# vl822.net
KiCad netlist of a schematic drawn in Altium Designer
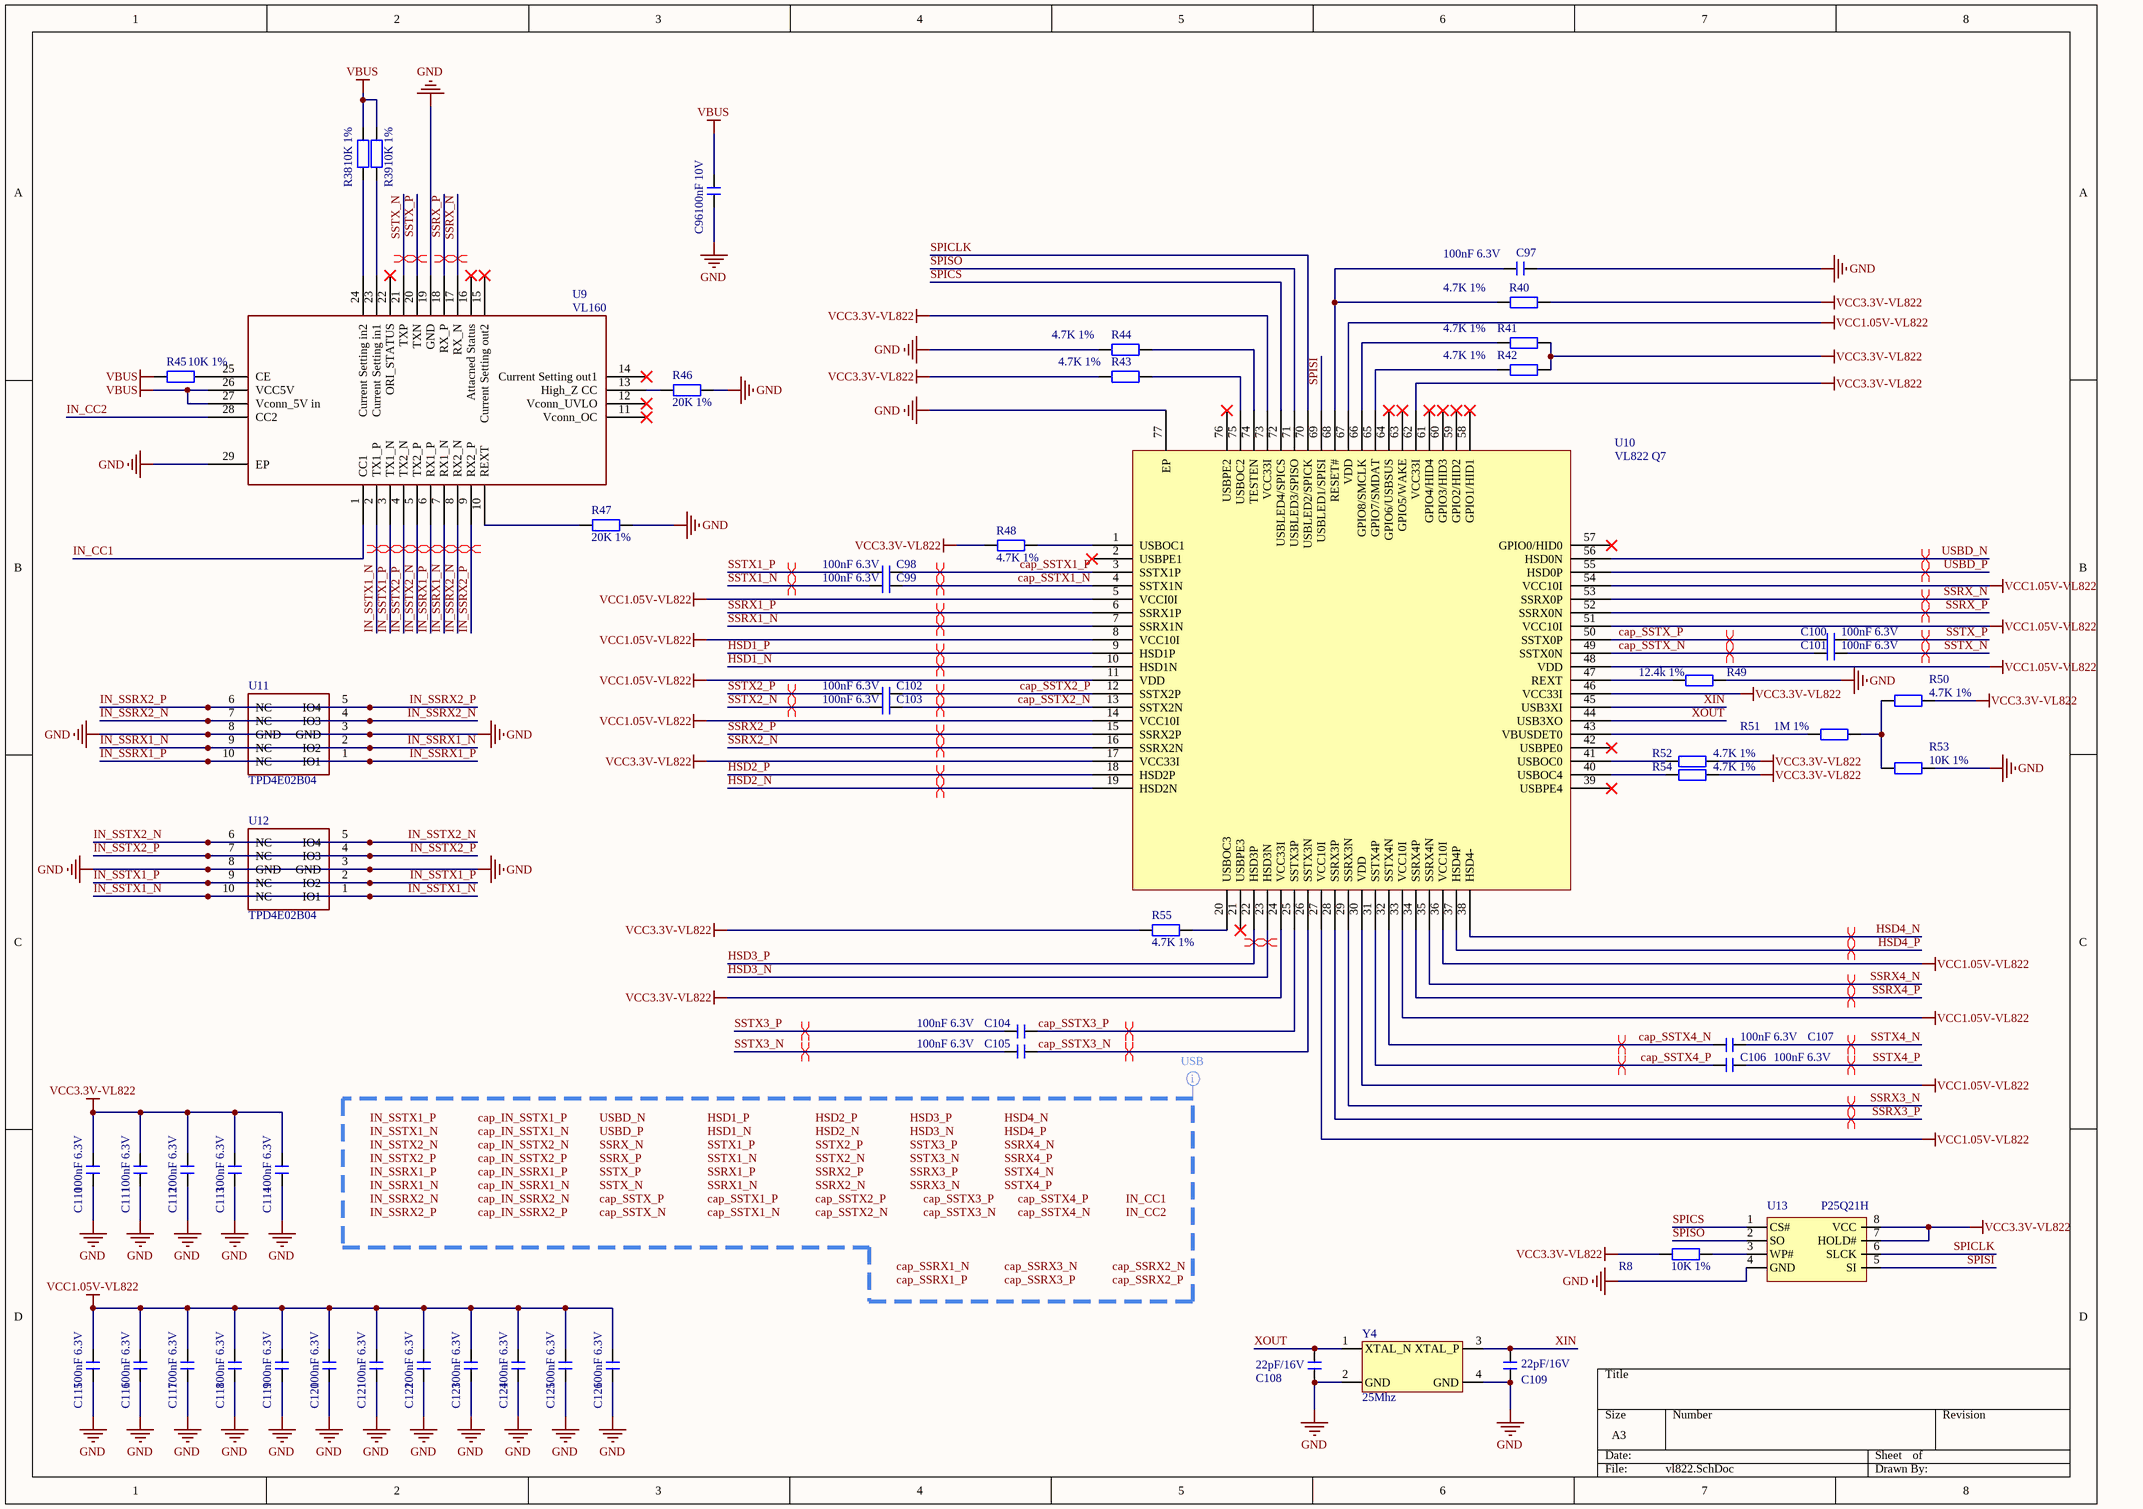
[diagram p0: vl822.SchDoc]

(export (version "E")
  (design (tool "Eeschema 10.0.6"))
  (components
    (comp (ref "C96")
      (value "100nF 10V")
      (footprint "C0402_L")
      (description "无极性贴片电容")
      (fields (field (name "版权归属") "源创客"))
      (libsource (lib "Capacitor") (part "C"))
    )
    (comp (ref "C97")
      (value "100nF 6.3V")
      (footprint "C0402_L")
      (description "无极性贴片电容")
      (fields (field (name "版权归属") "源创客"))
      (libsource (lib "Capacitor") (part "C"))
    )
    (comp (ref "C98")
      (value "100nF 6.3V")
      (footprint "C0402_L")
      (description "无极性贴片电容")
      (fields (field (name "版权归属") "源创客"))
      (libsource (lib "Capacitor") (part "C"))
    )
    (comp (ref "C99")
      (value "100nF 6.3V")
      (footprint "C0402_L")
      (description "无极性贴片电容")
      (fields (field (name "版权归属") "源创客"))
      (libsource (lib "Capacitor") (part "C"))
    )
    (comp (ref "C100")
      (value "100nF 6.3V")
      (footprint "C0402_L")
      (description "无极性贴片电容")
      (fields (field (name "版权归属") "源创客"))
      (libsource (lib "Capacitor") (part "C"))
    )
    (comp (ref "C101")
      (value "100nF 6.3V")
      (footprint "C0402_L")
      (description "无极性贴片电容")
      (fields (field (name "版权归属") "源创客"))
      (libsource (lib "Capacitor") (part "C"))
    )
    (comp (ref "C102")
      (value "100nF 6.3V")
      (footprint "C0402_L")
      (description "无极性贴片电容")
      (fields (field (name "版权归属") "源创客"))
      (libsource (lib "Capacitor") (part "C"))
    )
    (comp (ref "C103")
      (value "100nF 6.3V")
      (footprint "C0402_L")
      (description "无极性贴片电容")
      (fields (field (name "版权归属") "源创客"))
      (libsource (lib "Capacitor") (part "C"))
    )
    (comp (ref "C104")
      (value "100nF 6.3V")
      (footprint "C0402_L")
      (description "无极性贴片电容")
      (fields (field (name "版权归属") "源创客"))
      (libsource (lib "Capacitor") (part "C"))
    )
    (comp (ref "C105")
      (value "100nF 6.3V")
      (footprint "C0402_L")
      (description "无极性贴片电容")
      (fields (field (name "版权归属") "源创客"))
      (libsource (lib "Capacitor") (part "C"))
    )
    (comp (ref "C106")
      (value "100nF 6.3V")
      (footprint "C0402_L")
      (description "无极性贴片电容")
      (fields (field (name "版权归属") "源创客"))
      (libsource (lib "Capacitor") (part "C"))
    )
    (comp (ref "C107")
      (value "100nF 6.3V")
      (footprint "C0402_L")
      (description "无极性贴片电容")
      (fields (field (name "版权归属") "源创客"))
      (libsource (lib "Capacitor") (part "C"))
    )
    (comp (ref "C108")
      (value "22pF/16V")
      (footprint "C0402_L")
      (description "无极性贴片电容")
      (fields (field (name "版权归属") "源创客"))
      (libsource (lib "Capacitor") (part "C"))
    )
    (comp (ref "C109")
      (value "22pF/16V")
      (footprint "C0402_L")
      (description "无极性贴片电容")
      (fields (field (name "版权归属") "源创客"))
      (libsource (lib "Capacitor") (part "C"))
    )
    (comp (ref "C110")
      (value "100nF 6.3V")
      (footprint "C0402_L")
      (description "无极性贴片电容")
      (fields (field (name "版权归属") "源创客"))
      (libsource (lib "Capacitor") (part "C"))
    )
    (comp (ref "C111")
      (value "100nF 6.3V")
      (footprint "C0402_L")
      (description "无极性贴片电容")
      (fields (field (name "版权归属") "源创客"))
      (libsource (lib "Capacitor") (part "C"))
    )
    (comp (ref "C112")
      (value "100nF 6.3V")
      (footprint "C0402_L")
      (description "无极性贴片电容")
      (fields (field (name "版权归属") "源创客"))
      (libsource (lib "Capacitor") (part "C"))
    )
    (comp (ref "C113")
      (value "100nF 6.3V")
      (footprint "C0402_L")
      (description "无极性贴片电容")
      (fields (field (name "版权归属") "源创客"))
      (libsource (lib "Capacitor") (part "C"))
    )
    (comp (ref "C114")
      (value "100nF 6.3V")
      (footprint "C0402_L")
      (description "无极性贴片电容")
      (fields (field (name "版权归属") "源创客"))
      (libsource (lib "Capacitor") (part "C"))
    )
    (comp (ref "C115")
      (value "100nF 6.3V")
      (footprint "C0402_L")
      (description "无极性贴片电容")
      (fields (field (name "版权归属") "源创客"))
      (libsource (lib "Capacitor") (part "C"))
    )
    (comp (ref "C116")
      (value "100nF 6.3V")
      (footprint "C0402_L")
      (description "无极性贴片电容")
      (fields (field (name "版权归属") "源创客"))
      (libsource (lib "Capacitor") (part "C"))
    )
    (comp (ref "C117")
      (value "100nF 6.3V")
      (footprint "C0402_L")
      (description "无极性贴片电容")
      (fields (field (name "版权归属") "源创客"))
      (libsource (lib "Capacitor") (part "C"))
    )
    (comp (ref "C118")
      (value "100nF 6.3V")
      (footprint "C0402_L")
      (description "无极性贴片电容")
      (fields (field (name "版权归属") "源创客"))
      (libsource (lib "Capacitor") (part "C"))
    )
    (comp (ref "C119")
      (value "100nF 6.3V")
      (footprint "C0402_L")
      (description "无极性贴片电容")
      (fields (field (name "版权归属") "源创客"))
      (libsource (lib "Capacitor") (part "C"))
    )
    (comp (ref "C120")
      (value "100nF 6.3V")
      (footprint "C0402_L")
      (description "无极性贴片电容")
      (fields (field (name "版权归属") "源创客"))
      (libsource (lib "Capacitor") (part "C"))
    )
    (comp (ref "C121")
      (value "100nF 6.3V")
      (footprint "C0402_L")
      (description "无极性贴片电容")
      (fields (field (name "版权归属") "源创客"))
      (libsource (lib "Capacitor") (part "C"))
    )
    (comp (ref "C122")
      (value "100nF 6.3V")
      (footprint "C0402_L")
      (description "无极性贴片电容")
      (fields (field (name "版权归属") "源创客"))
      (libsource (lib "Capacitor") (part "C"))
    )
    (comp (ref "C123")
      (value "100nF 6.3V")
      (footprint "C0402_L")
      (description "无极性贴片电容")
      (fields (field (name "版权归属") "源创客"))
      (libsource (lib "Capacitor") (part "C"))
    )
    (comp (ref "C124")
      (value "100nF 6.3V")
      (footprint "C0402_L")
      (description "无极性贴片电容")
      (fields (field (name "版权归属") "源创客"))
      (libsource (lib "Capacitor") (part "C"))
    )
    (comp (ref "C125")
      (value "100nF 6.3V")
      (footprint "C0402_L")
      (description "无极性贴片电容")
      (fields (field (name "版权归属") "源创客"))
      (libsource (lib "Capacitor") (part "C"))
    )
    (comp (ref "C126")
      (value "100nF 6.3V")
      (footprint "C0402_L")
      (description "无极性贴片电容")
      (fields (field (name "版权归属") "源创客"))
      (libsource (lib "Capacitor") (part "C"))
    )
    (comp (ref "R8")
      (value "10K 1%")
      (footprint "R0402_L")
      (description "贴片电阻")
      (fields (field (name "版权归属") "源创客"))
      (libsource (lib "Resistor") (part "R"))
    )
    (comp (ref "R38")
      (value "10K 1%")
      (footprint "R0402_L")
      (description "贴片电阻")
      (fields (field (name "版权归属") "源创客"))
      (libsource (lib "Resistor") (part "R"))
    )
    (comp (ref "R39")
      (value "10K 1%")
      (footprint "R0402_L")
      (description "贴片电阻")
      (fields (field (name "版权归属") "源创客"))
      (libsource (lib "Resistor") (part "R"))
    )
    (comp (ref "R40")
      (value "4.7K 1%")
      (footprint "R0402_L")
      (description "贴片电阻")
      (fields (field (name "版权归属") "源创客"))
      (libsource (lib "Resistor") (part "R"))
    )
    (comp (ref "R41")
      (value "4.7K 1%")
      (footprint "R0402_L")
      (description "贴片电阻")
      (fields (field (name "版权归属") "源创客"))
      (libsource (lib "Resistor") (part "R"))
    )
    (comp (ref "R42")
      (value "4.7K 1%")
      (footprint "R0402_L")
      (description "贴片电阻")
      (fields (field (name "版权归属") "源创客"))
      (libsource (lib "Resistor") (part "R"))
    )
    (comp (ref "R43")
      (value "4.7K 1%")
      (footprint "R0402_L")
      (description "贴片电阻")
      (fields (field (name "版权归属") "源创客"))
      (libsource (lib "Resistor") (part "R"))
    )
    (comp (ref "R44")
      (value "4.7K 1%")
      (footprint "R0402_L")
      (description "贴片电阻")
      (fields (field (name "版权归属") "源创客"))
      (libsource (lib "Resistor") (part "R"))
    )
    (comp (ref "R45")
      (value "10K 1%")
      (footprint "R0402_L")
      (description "贴片电阻")
      (fields (field (name "版权归属") "源创客"))
      (libsource (lib "Resistor") (part "R"))
    )
    (comp (ref "R46")
      (value "20K 1%")
      (footprint "R0402_L")
      (description "贴片电阻")
      (fields (field (name "版权归属") "源创客"))
      (libsource (lib "Resistor") (part "R"))
    )
    (comp (ref "R47")
      (value "20K 1%")
      (footprint "R0402_L")
      (description "贴片电阻")
      (fields (field (name "版权归属") "源创客"))
      (libsource (lib "Resistor") (part "R"))
    )
    (comp (ref "R48")
      (value "4.7K 1%")
      (footprint "R0402_L")
      (description "贴片电阻")
      (fields (field (name "版权归属") "源创客"))
      (libsource (lib "Resistor") (part "R"))
    )
    (comp (ref "R49")
      (value "12.4k 1%")
      (footprint "R0402_L")
      (description "贴片电阻")
      (fields (field (name "版权归属") "源创客"))
      (libsource (lib "Resistor") (part "R"))
    )
    (comp (ref "R50")
      (value "4.7K 1%")
      (footprint "R0402_L")
      (description "贴片电阻")
      (fields (field (name "版权归属") "源创客"))
      (libsource (lib "Resistor") (part "R"))
    )
    (comp (ref "R51")
      (value "1M 1%")
      (footprint "R0402_L")
      (description "贴片电阻")
      (fields (field (name "版权归属") "源创客"))
      (libsource (lib "Resistor") (part "R"))
    )
    (comp (ref "R52")
      (value "4.7K 1%")
      (footprint "R0402_L")
      (description "贴片电阻")
      (fields (field (name "版权归属") "源创客"))
      (libsource (lib "Resistor") (part "R"))
    )
    (comp (ref "R53")
      (value "10K 1%")
      (footprint "R0402_L")
      (description "贴片电阻")
      (fields (field (name "版权归属") "源创客"))
      (libsource (lib "Resistor") (part "R"))
    )
    (comp (ref "R54")
      (value "4.7K 1%")
      (footprint "R0402_L")
      (description "贴片电阻")
      (fields (field (name "版权归属") "源创客"))
      (libsource (lib "Resistor") (part "R"))
    )
    (comp (ref "R55")
      (value "4.7K 1%")
      (footprint "R0402_L")
      (description "贴片电阻")
      (fields (field (name "版权归属") "源创客"))
      (libsource (lib "Resistor") (part "R"))
    )
    (comp (ref "U9")
      (value "VL160")
      (footprint "MQFN-28_L4.5-W3.5-P0.40-BL-EP")
      (libsource (lib "Brage") (part "VL160"))
    )
    (comp (ref "U10")
      (value "VL822 Q7")
      (footprint "QFN-76_L9.0-W9.0-P0.40-EP6.3-TL")
      (libsource (lib "Brage") (part "VL822 Q7"))
    )
    (comp (ref "U11")
      (value "TPD4E02B04")
      (footprint "DIO_TPD4E02B04DQAR")
      (description "ESD")
      (libsource (lib "Diode") (part "TPD4E02B04"))
    )
    (comp (ref "U12")
      (value "TPD4E02B04")
      (footprint "DIO_TPD4E02B04DQAR")
      (description "ESD")
      (libsource (lib "Diode") (part "TPD4E02B04"))
    )
    (comp (ref "U13") (value "P25Q21H") (footprint "SOP8_L") (libsource (lib "Flash") (part "P25D40H")))
    (comp (ref "Y4") (value "25Mhz") (footprint "OSC 3225-4P") (libsource (lib "Crystal") (part "Crystal")))
  )
  (nets
    (net (code "1") (name "/HSD1_N") (class "Default")
      (node (ref "U10") (pin "10") (pinfunction "HSD1N_10") (pintype "passive"))
    )
    (net (code "2") (name "/HSD1_P") (class "Default")
      (node (ref "U10") (pin "9") (pinfunction "HSD1P_9") (pintype "passive"))
    )
    (net (code "3") (name "/HSD2_N") (class "Default")
      (node (ref "U10") (pin "19") (pinfunction "HSD2N_19") (pintype "passive"))
    )
    (net (code "4") (name "/HSD2_P") (class "Default")
      (node (ref "U10") (pin "18") (pinfunction "HSD2P_18") (pintype "passive"))
    )
    (net (code "5") (name "/HSD3_N") (class "Default")
      (node (ref "U10") (pin "23") (pinfunction "HSD3N_23") (pintype "passive"))
    )
    (net (code "6") (name "/HSD3_P") (class "Default")
      (node (ref "U10") (pin "22") (pinfunction "HSD3P_22") (pintype "passive"))
    )
    (net (code "7") (name "/HSD4_N") (class "Default")
      (node (ref "U10") (pin "38") (pinfunction "HSD4-_38") (pintype "passive"))
    )
    (net (code "8") (name "/HSD4_P") (class "Default")
      (node (ref "U10") (pin "37") (pinfunction "HSD4P_37") (pintype "passive"))
    )
    (net (code "9") (name "/IN_CC1") (class "Default")
      (node (ref "U9") (pin "1") (pinfunction "CC1_1") (pintype "passive"))
    )
    (net (code "10") (name "/IN_CC2") (class "Default")
      (node (ref "U9") (pin "28") (pinfunction "CC2_28") (pintype "passive"))
    )
    (net (code "11") (name "/IN_SSRX1_N") (class "Default")
      (node (ref "U11") (pin "2") (pinfunction "IO2_2") (pintype "passive"))
      (node (ref "U11") (pin "9") (pinfunction "NC_9") (pintype "passive"))
      (node (ref "U9") (pin "7") (pinfunction "RX1_N_7") (pintype "passive"))
    )
    (net (code "12") (name "/IN_SSRX1_P") (class "Default")
      (node (ref "U11") (pin "1") (pinfunction "IO1_1") (pintype "passive"))
      (node (ref "U11") (pin "10") (pinfunction "NC_10") (pintype "passive"))
      (node (ref "U9") (pin "6") (pinfunction "RX1_P_6") (pintype "passive"))
    )
    (net (code "13") (name "/IN_SSRX2_N") (class "Default")
      (node (ref "U11") (pin "4") (pinfunction "IO3_4") (pintype "passive"))
      (node (ref "U11") (pin "7") (pinfunction "NC_7") (pintype "passive"))
      (node (ref "U9") (pin "8") (pinfunction "RX2_N_8") (pintype "passive"))
    )
    (net (code "14") (name "/IN_SSRX2_P") (class "Default")
      (node (ref "U11") (pin "5") (pinfunction "IO4_5") (pintype "passive"))
      (node (ref "U11") (pin "6") (pinfunction "NC_6") (pintype "passive"))
      (node (ref "U9") (pin "9") (pinfunction "RX2_P_9") (pintype "passive"))
    )
    (net (code "15") (name "/IN_SSTX1_N") (class "Default")
      (node (ref "U12") (pin "1") (pinfunction "IO1_1") (pintype "passive"))
      (node (ref "U12") (pin "10") (pinfunction "NC_10") (pintype "passive"))
      (node (ref "U9") (pin "2") (pinfunction "TX1_P_2") (pintype "passive"))
    )
    (net (code "16") (name "/IN_SSTX1_P") (class "Default")
      (node (ref "U12") (pin "2") (pinfunction "IO2_2") (pintype "passive"))
      (node (ref "U12") (pin "9") (pinfunction "NC_9") (pintype "passive"))
      (node (ref "U9") (pin "3") (pinfunction "TX1_N_3") (pintype "passive"))
    )
    (net (code "17") (name "/IN_SSTX2_N") (class "Default")
      (node (ref "U12") (pin "5") (pinfunction "IO4_5") (pintype "passive"))
      (node (ref "U12") (pin "6") (pinfunction "NC_6") (pintype "passive"))
      (node (ref "U9") (pin "5") (pinfunction "TX2_P_5") (pintype "passive"))
    )
    (net (code "18") (name "/IN_SSTX2_P") (class "Default")
      (node (ref "U12") (pin "4") (pinfunction "IO3_4") (pintype "passive"))
      (node (ref "U12") (pin "7") (pinfunction "NC_7") (pintype "passive"))
      (node (ref "U9") (pin "4") (pinfunction "TX2_N_4") (pintype "passive"))
    )
    (net (code "19") (name "/SPICLK") (class "Default")
      (node (ref "U10") (pin "70") (pinfunction "USBLED2/SPICK_70") (pintype "passive"))
      (node (ref "U13") (pin "6") (pinfunction "SLCK_6") (pintype "passive"))
    )
    (net (code "20") (name "/SPICS") (class "Default")
      (node (ref "U10") (pin "72") (pinfunction "USBLED4/SPICS_72") (pintype "passive"))
      (node (ref "U13") (pin "1") (pinfunction "CS#_1") (pintype "passive"))
    )
    (net (code "21") (name "/SPISI") (class "Default")
      (node (ref "U10") (pin "69") (pinfunction "USBLED1/SPISI_69") (pintype "passive"))
      (node (ref "U13") (pin "5") (pinfunction "SI_5") (pintype "passive"))
    )
    (net (code "22") (name "/SPISO") (class "Default")
      (node (ref "U10") (pin "71") (pinfunction "USBLED3/SPISO_71") (pintype "passive"))
      (node (ref "U13") (pin "2") (pinfunction "SO_2") (pintype "passive"))
    )
    (net (code "23") (name "/SSRX1_N") (class "Default")
      (node (ref "U10") (pin "7") (pinfunction "SSRX1N_7") (pintype "passive"))
    )
    (net (code "24") (name "/SSRX1_P") (class "Default")
      (node (ref "U10") (pin "6") (pinfunction "SSRX1P_6") (pintype "passive"))
    )
    (net (code "25") (name "/SSRX2_N") (class "Default")
      (node (ref "U10") (pin "16") (pinfunction "SSRX2N_16") (pintype "passive"))
    )
    (net (code "26") (name "/SSRX2_P") (class "Default")
      (node (ref "U10") (pin "15") (pinfunction "SSRX2P_15") (pintype "passive"))
    )
    (net (code "27") (name "/SSRX3_N") (class "Default")
      (node (ref "U10") (pin "29") (pinfunction "SSRX3N_29") (pintype "passive"))
    )
    (net (code "28") (name "/SSRX3_P") (class "Default")
      (node (ref "U10") (pin "28") (pinfunction "SSRX3P_28") (pintype "passive"))
    )
    (net (code "29") (name "/SSRX4_N") (class "Default")
      (node (ref "U10") (pin "35") (pinfunction "SSRX4N_35") (pintype "passive"))
    )
    (net (code "30") (name "/SSRX4_P") (class "Default")
      (node (ref "U10") (pin "34") (pinfunction "SSRX4P_34") (pintype "passive"))
    )
    (net (code "31") (name "/SSRX_N") (class "Default")
      (node (ref "U10") (pin "53") (pinfunction "SSRX0P_53") (pintype "passive"))
      (node (ref "U9") (pin "17") (pinfunction "RX_N_17") (pintype "passive"))
    )
    (net (code "32") (name "/SSRX_P") (class "Default")
      (node (ref "U10") (pin "52") (pinfunction "SSRX0N_52") (pintype "passive"))
      (node (ref "U9") (pin "18") (pinfunction "RX_P_18") (pintype "passive"))
    )
    (net (code "33") (name "/SSTX1_N") (class "Default")
      (node (ref "C99") (pin "1") (pinfunction "1_1") (pintype "passive"))
    )
    (net (code "34") (name "/SSTX1_P") (class "Default")
      (node (ref "C98") (pin "1") (pinfunction "1_1") (pintype "passive"))
    )
    (net (code "35") (name "/SSTX2_N") (class "Default")
      (node (ref "C103") (pin "1") (pinfunction "1_1") (pintype "passive"))
    )
    (net (code "36") (name "/SSTX2_P") (class "Default")
      (node (ref "C102") (pin "1") (pinfunction "1_1") (pintype "passive"))
    )
    (net (code "37") (name "/SSTX3_N") (class "Default")
      (node (ref "C105") (pin "1") (pinfunction "1_1") (pintype "passive"))
    )
    (net (code "38") (name "/SSTX3_P") (class "Default")
      (node (ref "C104") (pin "1") (pinfunction "1_1") (pintype "passive"))
    )
    (net (code "39") (name "/SSTX4_N") (class "Default")
      (node (ref "C107") (pin "1") (pinfunction "1_1") (pintype "passive"))
    )
    (net (code "40") (name "/SSTX4_P") (class "Default")
      (node (ref "C106") (pin "1") (pinfunction "1_1") (pintype "passive"))
    )
    (net (code "41") (name "/SSTX_N") (class "Default")
      (node (ref "C101") (pin "1") (pinfunction "1_1") (pintype "passive"))
      (node (ref "U9") (pin "21") (pinfunction "TXP_21") (pintype "passive"))
    )
    (net (code "42") (name "/SSTX_P") (class "Default")
      (node (ref "C100") (pin "1") (pinfunction "1_1") (pintype "passive"))
      (node (ref "U9") (pin "20") (pinfunction "TXN_20") (pintype "passive"))
    )
    (net (code "43") (name "/USBD_N") (class "Default")
      (node (ref "U10") (pin "56") (pinfunction "HSD0N_56") (pintype "passive"))
    )
    (net (code "44") (name "/USBD_P") (class "Default")
      (node (ref "U10") (pin "55") (pinfunction "HSD0P_55") (pintype "passive"))
    )
    (net (code "45") (name "/XIN") (class "Default")
      (node (ref "C109") (pin "1") (pinfunction "1_1") (pintype "passive"))
      (node (ref "U10") (pin "45") (pinfunction "USB3XI_45") (pintype "passive"))
      (node (ref "Y4") (pin "3") (pinfunction "XTAL_P_3") (pintype "passive"))
    )
    (net (code "46") (name "/XOUT") (class "Default")
      (node (ref "C108") (pin "1") (pinfunction "1_1") (pintype "passive"))
      (node (ref "U10") (pin "44") (pinfunction "USB3XO_44") (pintype "passive"))
      (node (ref "Y4") (pin "1") (pinfunction "XTAL_N_1") (pintype "passive"))
    )
    (net (code "61") (name "/cap_SSTX1_N") (class "Default")
      (node (ref "C99") (pin "2") (pinfunction "2_2") (pintype "passive"))
      (node (ref "U10") (pin "4") (pinfunction "SSTX1N_4") (pintype "passive"))
    )
    (net (code "62") (name "/cap_SSTX1_P") (class "Default")
      (node (ref "C98") (pin "2") (pinfunction "2_2") (pintype "passive"))
      (node (ref "U10") (pin "3") (pinfunction "SSTX1P_3") (pintype "passive"))
    )
    (net (code "63") (name "/cap_SSTX2_N") (class "Default")
      (node (ref "C103") (pin "2") (pinfunction "2_2") (pintype "passive"))
      (node (ref "U10") (pin "13") (pinfunction "SSTX2N_13") (pintype "passive"))
    )
    (net (code "64") (name "/cap_SSTX2_P") (class "Default")
      (node (ref "C102") (pin "2") (pinfunction "2_2") (pintype "passive"))
      (node (ref "U10") (pin "12") (pinfunction "SSTX2P_12") (pintype "passive"))
    )
    (net (code "65") (name "/cap_SSTX3_N") (class "Default")
      (node (ref "C105") (pin "2") (pinfunction "2_2") (pintype "passive"))
      (node (ref "U10") (pin "26") (pinfunction "SSTX3N_26") (pintype "passive"))
    )
    (net (code "66") (name "/cap_SSTX3_P") (class "Default")
      (node (ref "C104") (pin "2") (pinfunction "2_2") (pintype "passive"))
      (node (ref "U10") (pin "25") (pinfunction "SSTX3P_25") (pintype "passive"))
    )
    (net (code "67") (name "/cap_SSTX4_N") (class "Default")
      (node (ref "C107") (pin "2") (pinfunction "2_2") (pintype "passive"))
      (node (ref "U10") (pin "32") (pinfunction "SSTX4N_32") (pintype "passive"))
    )
    (net (code "68") (name "/cap_SSTX4_P") (class "Default")
      (node (ref "C106") (pin "2") (pinfunction "2_2") (pintype "passive"))
      (node (ref "U10") (pin "31") (pinfunction "SSTX4P_31") (pintype "passive"))
    )
    (net (code "69") (name "/cap_SSTX_N") (class "Default")
      (node (ref "C101") (pin "2") (pinfunction "2_2") (pintype "passive"))
      (node (ref "U10") (pin "49") (pinfunction "SSTX0N_49") (pintype "passive"))
    )
    (net (code "70") (name "/cap_SSTX_P") (class "Default")
      (node (ref "C100") (pin "2") (pinfunction "2_2") (pintype "passive"))
      (node (ref "U10") (pin "50") (pinfunction "SSTX0P_50") (pintype "passive"))
    )
    (net (code "71") (name "GND") (class "Default")
      (node (ref "C108") (pin "2") (pinfunction "2_2") (pintype "passive"))
      (node (ref "C109") (pin "2") (pinfunction "2_2") (pintype "passive"))
      (node (ref "C110") (pin "1") (pinfunction "1_1") (pintype "passive"))
      (node (ref "C111") (pin "1") (pinfunction "1_1") (pintype "passive"))
      (node (ref "C112") (pin "1") (pinfunction "1_1") (pintype "passive"))
      (node (ref "C113") (pin "1") (pinfunction "1_1") (pintype "passive"))
      (node (ref "C114") (pin "1") (pinfunction "1_1") (pintype "passive"))
      (node (ref "C115") (pin "1") (pinfunction "1_1") (pintype "passive"))
      (node (ref "C116") (pin "1") (pinfunction "1_1") (pintype "passive"))
      (node (ref "C117") (pin "1") (pinfunction "1_1") (pintype "passive"))
      (node (ref "C118") (pin "1") (pinfunction "1_1") (pintype "passive"))
      (node (ref "C119") (pin "1") (pinfunction "1_1") (pintype "passive"))
      (node (ref "C120") (pin "1") (pinfunction "1_1") (pintype "passive"))
      (node (ref "C121") (pin "1") (pinfunction "1_1") (pintype "passive"))
      (node (ref "C122") (pin "1") (pinfunction "1_1") (pintype "passive"))
      (node (ref "C123") (pin "1") (pinfunction "1_1") (pintype "passive"))
      (node (ref "C124") (pin "1") (pinfunction "1_1") (pintype "passive"))
      (node (ref "C125") (pin "1") (pinfunction "1_1") (pintype "passive"))
      (node (ref "C126") (pin "1") (pinfunction "1_1") (pintype "passive"))
      (node (ref "C96") (pin "1") (pinfunction "1_1") (pintype "passive"))
      (node (ref "C97") (pin "2") (pinfunction "2_2") (pintype "passive"))
      (node (ref "R44") (pin "2") (pinfunction "2_2") (pintype "passive"))
      (node (ref "R46") (pin "1") (pinfunction "1_1") (pintype "passive"))
      (node (ref "R47") (pin "1") (pinfunction "1_1") (pintype "passive"))
      (node (ref "R49") (pin "2") (pinfunction "2_2") (pintype "passive"))
      (node (ref "R53") (pin "2") (pinfunction "2_2") (pintype "passive"))
      (node (ref "U10") (pin "77") (pinfunction "EP_77") (pintype "passive"))
      (node (ref "U11") (pin "3") (pinfunction "GND_3") (pintype "passive"))
      (node (ref "U11") (pin "8") (pinfunction "GND_8") (pintype "passive"))
      (node (ref "U12") (pin "3") (pinfunction "GND_3") (pintype "passive"))
      (node (ref "U12") (pin "8") (pinfunction "GND_8") (pintype "passive"))
      (node (ref "U13") (pin "4") (pinfunction "GND_4") (pintype "passive"))
      (node (ref "U9") (pin "19") (pinfunction "GND_19") (pintype "passive"))
      (node (ref "U9") (pin "29") (pinfunction "EP_29") (pintype "passive"))
      (node (ref "Y4") (pin "2") (pinfunction "GND_2") (pintype "passive"))
      (node (ref "Y4") (pin "4") (pinfunction "GND_4") (pintype "passive"))
    )
    (net (code "72") (name "Net-(R50-Pad1)") (class "Default")
      (node (ref "R50") (pin "1") (pinfunction "1_1") (pintype "passive"))
      (node (ref "R51") (pin "2") (pinfunction "2_2") (pintype "passive"))
      (node (ref "R53") (pin "1") (pinfunction "1_1") (pintype "passive"))
    )
    (net (code "73") (name "Net-(U9-CE)") (class "Default")
      (node (ref "R45") (pin "1") (pinfunction "1_1") (pintype "passive"))
      (node (ref "U9") (pin "25") (pinfunction "CE_25") (pintype "passive"))
    )
    (net (code "74") (name "Net-(U9-Current_Setting_in1)") (class "Default")
      (node (ref "R39") (pin "2") (pinfunction "2_2") (pintype "passive"))
      (node (ref "U9") (pin "23") (pinfunction "Current_Setting_in1_23") (pintype "passive"))
    )
    (net (code "75") (name "Net-(U9-Current_Setting_in2)") (class "Default")
      (node (ref "R38") (pin "2") (pinfunction "2_2") (pintype "passive"))
      (node (ref "U9") (pin "24") (pinfunction "Current_Setting_in2_24") (pintype "passive"))
    )
    (net (code "76") (name "Net-(U9-High_Z_CC)") (class "Default")
      (node (ref "R46") (pin "2") (pinfunction "2_2") (pintype "passive"))
      (node (ref "U9") (pin "13") (pinfunction "High_Z_CC_13") (pintype "passive"))
    )
    (net (code "77") (name "Net-(U9-REXT)") (class "Default")
      (node (ref "R47") (pin "2") (pinfunction "2_2") (pintype "passive"))
      (node (ref "U9") (pin "10") (pinfunction "REXT_10") (pintype "passive"))
    )
    (net (code "78") (name "Net-(U10-GPIO7{slash}SMDAT)") (class "Default")
      (node (ref "R42") (pin "1") (pinfunction "1_1") (pintype "passive"))
      (node (ref "U10") (pin "65") (pinfunction "GPIO7/SMDAT_65") (pintype "passive"))
    )
    (net (code "79") (name "Net-(U10-GPIO8{slash}SMCLK)") (class "Default")
      (node (ref "R41") (pin "1") (pinfunction "1_1") (pintype "passive"))
      (node (ref "U10") (pin "66") (pinfunction "GPIO8/SMCLK_66") (pintype "passive"))
    )
    (net (code "80") (name "Net-(U10-RESET#)") (class "Default")
      (node (ref "C97") (pin "1") (pinfunction "1_1") (pintype "passive"))
      (node (ref "R40") (pin "1") (pinfunction "1_1") (pintype "passive"))
      (node (ref "U10") (pin "68") (pinfunction "RESET#_68") (pintype "passive"))
    )
    (net (code "81") (name "Net-(U10-REXT)") (class "Default")
      (node (ref "R49") (pin "1") (pinfunction "1_1") (pintype "passive"))
      (node (ref "U10") (pin "47") (pinfunction "REXT_47") (pintype "passive"))
    )
    (net (code "82") (name "Net-(U10-TESTEN)") (class "Default")
      (node (ref "R44") (pin "1") (pinfunction "1_1") (pintype "passive"))
      (node (ref "U10") (pin "74") (pinfunction "TESTEN_74") (pintype "passive"))
    )
    (net (code "83") (name "Net-(U10-USBOC0)") (class "Default")
      (node (ref "R52") (pin "1") (pinfunction "1_1") (pintype "passive"))
      (node (ref "U10") (pin "41") (pinfunction "USBOC0_41") (pintype "passive"))
    )
    (net (code "84") (name "Net-(U10-USBOC1)") (class "Default")
      (node (ref "R48") (pin "1") (pinfunction "1_1") (pintype "passive"))
      (node (ref "U10") (pin "1") (pinfunction "USBOC1_1") (pintype "passive"))
    )
    (net (code "85") (name "Net-(U10-USBOC2)") (class "Default")
      (node (ref "R43") (pin "1") (pinfunction "1_1") (pintype "passive"))
      (node (ref "U10") (pin "75") (pinfunction "USBOC2_75") (pintype "passive"))
    )
    (net (code "86") (name "Net-(U10-USBOC3)") (class "Default")
      (node (ref "R55") (pin "1") (pinfunction "1_1") (pintype "passive"))
      (node (ref "U10") (pin "20") (pinfunction "USBOC3_20") (pintype "passive"))
    )
    (net (code "87") (name "Net-(U10-USBOC4)") (class "Default")
      (node (ref "R54") (pin "1") (pinfunction "1_1") (pintype "passive"))
      (node (ref "U10") (pin "40") (pinfunction "USBOC4_40") (pintype "passive"))
    )
    (net (code "88") (name "Net-(U10-VBUSDET0)") (class "Default")
      (node (ref "R51") (pin "1") (pinfunction "1_1") (pintype "passive"))
      (node (ref "U10") (pin "43") (pinfunction "VBUSDET0_43") (pintype "passive"))
    )
    (net (code "89") (name "Net-(U13-WP#)") (class "Default")
      (node (ref "R8") (pin "1") (pinfunction "1_1") (pintype "passive"))
      (node (ref "U13") (pin "3") (pinfunction "WP#_3") (pintype "passive"))
    )
    (net (code "90") (name "VBUS") (class "Default")
      (node (ref "C96") (pin "2") (pinfunction "2_2") (pintype "passive"))
      (node (ref "R38") (pin "1") (pinfunction "1_1") (pintype "passive"))
      (node (ref "R39") (pin "1") (pinfunction "1_1") (pintype "passive"))
      (node (ref "R45") (pin "2") (pinfunction "2_2") (pintype "passive"))
      (node (ref "U9") (pin "26") (pinfunction "VCC5V_26") (pintype "passive"))
      (node (ref "U9") (pin "27") (pinfunction "Vconn_5V_in_27") (pintype "passive"))
    )
    (net (code "91") (name "VCC1.05V-VL822") (class "Default")
      (node (ref "C115") (pin "2") (pinfunction "2_2") (pintype "passive"))
      (node (ref "C116") (pin "2") (pinfunction "2_2") (pintype "passive"))
      (node (ref "C117") (pin "2") (pinfunction "2_2") (pintype "passive"))
      (node (ref "C118") (pin "2") (pinfunction "2_2") (pintype "passive"))
      (node (ref "C119") (pin "2") (pinfunction "2_2") (pintype "passive"))
      (node (ref "C120") (pin "2") (pinfunction "2_2") (pintype "passive"))
      (node (ref "C121") (pin "2") (pinfunction "2_2") (pintype "passive"))
      (node (ref "C122") (pin "2") (pinfunction "2_2") (pintype "passive"))
      (node (ref "C123") (pin "2") (pinfunction "2_2") (pintype "passive"))
      (node (ref "C124") (pin "2") (pinfunction "2_2") (pintype "passive"))
      (node (ref "C125") (pin "2") (pinfunction "2_2") (pintype "passive"))
      (node (ref "C126") (pin "2") (pinfunction "2_2") (pintype "passive"))
      (node (ref "U10") (pin "11") (pinfunction "VDD_11") (pintype "passive"))
      (node (ref "U10") (pin "14") (pinfunction "VCC10I_14") (pintype "passive"))
      (node (ref "U10") (pin "27") (pinfunction "VCC10I_27") (pintype "passive"))
      (node (ref "U10") (pin "30") (pinfunction "VDD_30") (pintype "passive"))
      (node (ref "U10") (pin "33") (pinfunction "VCC10I_33") (pintype "passive"))
      (node (ref "U10") (pin "36") (pinfunction "VCC10I_36") (pintype "passive"))
      (node (ref "U10") (pin "48") (pinfunction "VDD_48") (pintype "passive"))
      (node (ref "U10") (pin "5") (pinfunction "VCCI0I_5") (pintype "passive"))
      (node (ref "U10") (pin "51") (pinfunction "VCC10I_51") (pintype "passive"))
      (node (ref "U10") (pin "54") (pinfunction "VCC10I_54") (pintype "passive"))
      (node (ref "U10") (pin "67") (pinfunction "VDD_67") (pintype "passive"))
      (node (ref "U10") (pin "8") (pinfunction "VCC10I_8") (pintype "passive"))
    )
    (net (code "92") (name "VCC3.3V-VL822") (class "Default")
      (node (ref "C110") (pin "2") (pinfunction "2_2") (pintype "passive"))
      (node (ref "C111") (pin "2") (pinfunction "2_2") (pintype "passive"))
      (node (ref "C112") (pin "2") (pinfunction "2_2") (pintype "passive"))
      (node (ref "C113") (pin "2") (pinfunction "2_2") (pintype "passive"))
      (node (ref "C114") (pin "2") (pinfunction "2_2") (pintype "passive"))
      (node (ref "R40") (pin "2") (pinfunction "2_2") (pintype "passive"))
      (node (ref "R41") (pin "2") (pinfunction "2_2") (pintype "passive"))
      (node (ref "R42") (pin "2") (pinfunction "2_2") (pintype "passive"))
      (node (ref "R43") (pin "2") (pinfunction "2_2") (pintype "passive"))
      (node (ref "R48") (pin "2") (pinfunction "2_2") (pintype "passive"))
      (node (ref "R50") (pin "2") (pinfunction "2_2") (pintype "passive"))
      (node (ref "R52") (pin "2") (pinfunction "2_2") (pintype "passive"))
      (node (ref "R54") (pin "2") (pinfunction "2_2") (pintype "passive"))
      (node (ref "R55") (pin "2") (pinfunction "2_2") (pintype "passive"))
      (node (ref "R8") (pin "2") (pinfunction "2_2") (pintype "passive"))
      (node (ref "U10") (pin "17") (pinfunction "VCC33I_17") (pintype "passive"))
      (node (ref "U10") (pin "24") (pinfunction "VCC33I_24") (pintype "passive"))
      (node (ref "U10") (pin "46") (pinfunction "VCC33I_46") (pintype "passive"))
      (node (ref "U10") (pin "62") (pinfunction "VCC33I_62") (pintype "passive"))
      (node (ref "U10") (pin "73") (pinfunction "VCC33I_73") (pintype "passive"))
      (node (ref "U13") (pin "7") (pinfunction "HOLD#_7") (pintype "passive"))
      (node (ref "U13") (pin "8") (pinfunction "VCC_8") (pintype "passive"))
    )
    (net (code "93") (name "unconnected-(U9-Attacned_Status-Pad16)") (class "Default")
      (node (ref "U9") (pin "16") (pinfunction "Attacned_Status_16") (pintype "passive+no_connect"))
    )
    (net (code "94") (name "unconnected-(U9-Current_Setting_out1-Pad14)") (class "Default")
      (node (ref "U9") (pin "14") (pinfunction "Current_Setting_out1_14") (pintype "passive+no_connect"))
    )
    (net (code "95") (name "unconnected-(U9-Current_Setting_out2-Pad15)") (class "Default")
      (node (ref "U9") (pin "15") (pinfunction "Current_Setting_out2_15") (pintype "passive+no_connect"))
    )
    (net (code "96") (name "unconnected-(U9-ORI_STATUS-Pad22)") (class "Default")
      (node (ref "U9") (pin "22") (pinfunction "ORI_STATUS_22") (pintype "passive+no_connect"))
    )
    (net (code "97") (name "unconnected-(U9-Vconn_OC-Pad11)") (class "Default")
      (node (ref "U9") (pin "11") (pinfunction "Vconn_OC_11") (pintype "passive+no_connect"))
    )
    (net (code "98") (name "unconnected-(U9-Vconn_UVLO-Pad12)") (class "Default")
      (node (ref "U9") (pin "12") (pinfunction "Vconn_UVLO_12") (pintype "passive+no_connect"))
    )
    (net (code "99") (name "unconnected-(U10-GPIO0{slash}HID0-Pad57)") (class "Default")
      (node (ref "U10") (pin "57") (pinfunction "GPIO0/HID0_57") (pintype "passive+no_connect"))
    )
    (net (code "100") (name "unconnected-(U10-GPIO1{slash}HID1-Pad58)") (class "Default")
      (node (ref "U10") (pin "58") (pinfunction "GPIO1/HID1_58") (pintype "passive+no_connect"))
    )
    (net (code "101") (name "unconnected-(U10-GPIO2{slash}HID2-Pad59)") (class "Default")
      (node (ref "U10") (pin "59") (pinfunction "GPIO2/HID2_59") (pintype "passive+no_connect"))
    )
    (net (code "102") (name "unconnected-(U10-GPIO3{slash}HID3-Pad60)") (class "Default")
      (node (ref "U10") (pin "60") (pinfunction "GPIO3/HID3_60") (pintype "passive+no_connect"))
    )
    (net (code "103") (name "unconnected-(U10-GPIO4{slash}HID4-Pad61)") (class "Default")
      (node (ref "U10") (pin "61") (pinfunction "GPIO4/HID4_61") (pintype "passive+no_connect"))
    )
    (net (code "104") (name "unconnected-(U10-GPIO5{slash}WAKE-Pad63)") (class "Default")
      (node (ref "U10") (pin "63") (pinfunction "GPIO5/WAKE_63") (pintype "passive+no_connect"))
    )
    (net (code "105") (name "unconnected-(U10-GPIO6{slash}USBSUS-Pad64)") (class "Default")
      (node (ref "U10") (pin "64") (pinfunction "GPIO6/USBSUS_64") (pintype "passive+no_connect"))
    )
    (net (code "106") (name "unconnected-(U10-USBPE0-Pad42)") (class "Default")
      (node (ref "U10") (pin "42") (pinfunction "USBPE0_42") (pintype "passive+no_connect"))
    )
    (net (code "107") (name "unconnected-(U10-USBPE1-Pad2)") (class "Default")
      (node (ref "U10") (pin "2") (pinfunction "USBPE1_2") (pintype "passive+no_connect"))
    )
    (net (code "108") (name "unconnected-(U10-USBPE2-Pad76)") (class "Default")
      (node (ref "U10") (pin "76") (pinfunction "USBPE2_76") (pintype "passive+no_connect"))
    )
    (net (code "109") (name "unconnected-(U10-USBPE3-Pad21)") (class "Default")
      (node (ref "U10") (pin "21") (pinfunction "USBPE3_21") (pintype "passive+no_connect"))
    )
    (net (code "110") (name "unconnected-(U10-USBPE4-Pad39)") (class "Default")
      (node (ref "U10") (pin "39") (pinfunction "USBPE4_39") (pintype "passive+no_connect"))
    )
  )
)
